# MCU.net
KiCad netlist of a schematic drawn in Altium Designer
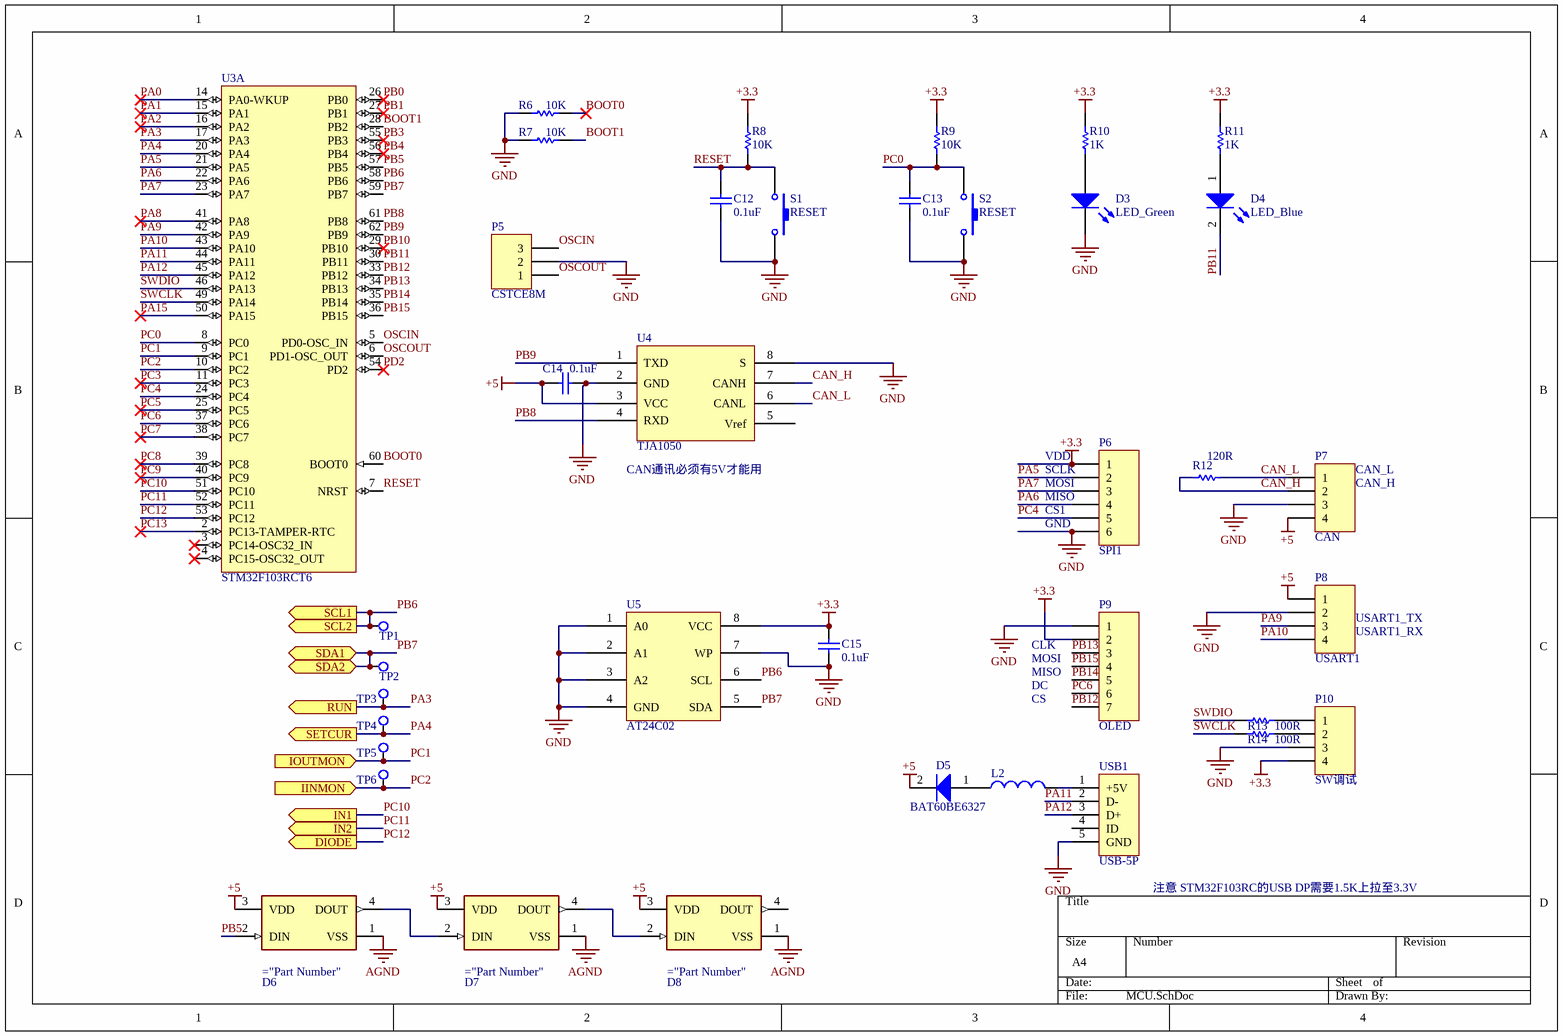
[diagram p0: MCU.SchDoc]

(export (version "E")
  (design (tool "Eeschema 10.0.6"))
  (components
    (comp (ref "C12")
      (value "0.1uF")
      (footprint "0603C")
      (description "X5R 50V")
      (fields (field (name "Comment") "Cap") (field (name "PUBLISHER") "Altium Limited"))
      (libsource (lib "Miscellaneous Devices") (part "Cap"))
    )
    (comp (ref "C13")
      (value "0.1uF")
      (footprint "0603C")
      (description "X5R 50V")
      (fields (field (name "Comment") "Cap") (field (name "PUBLISHER") "Altium Limited"))
      (libsource (lib "Miscellaneous Devices") (part "Cap"))
    )
    (comp (ref "C14")
      (value "0.1uF")
      (footprint "0603C")
      (description "X5R 50V")
      (fields (field (name "Comment") "Cap") (field (name "PUBLISHER") "Altium Limited"))
      (libsource (lib "Miscellaneous Devices") (part "Cap"))
    )
    (comp (ref "C15")
      (value "0.1uF")
      (footprint "0603C")
      (description "X5R 50V")
      (fields (field (name "Comment") "Cap") (field (name "PUBLISHER") "Altium Limited"))
      (libsource (lib "Miscellaneous Devices") (part "Cap"))
    )
    (comp (ref "D3")
      (value "LED_Green")
      (footprint "LED 0603B")
      (description "Green")
      (fields (field (name "PUBLISHER") "Altium Limited"))
      (libsource (lib "Miscellaneous Devices") (part "LED0"))
    )
    (comp (ref "D4")
      (value "LED_Blue")
      (footprint "LED 0603B")
      (description "Blue")
      (fields (field (name "PUBLISHER") "Altium Limited"))
      (libsource (lib "") (part "LED0_1"))
    )
    (comp (ref "D5")
      (value "BAT60BE6327")
      (footprint "SOD-523")
      (description "Diode")
      (fields (field (name "PUBLISHER") "Altium Limited"))
      (libsource (lib "Miscellaneous Devices") (part "Diode"))
    )
    (comp (ref "D6")
      (value "WS2812")
      (footprint "Adafruit_1655_0")
      (description "RGB LED")
      (libsource (lib "MiscDevices_SP") (part "WS2812"))
    )
    (comp (ref "D7")
      (value "WS2812")
      (footprint "Adafruit_1655_0")
      (description "RGB LED")
      (libsource (lib "MiscDevices_SP") (part "WS2812"))
    )
    (comp (ref "D8")
      (value "WS2812")
      (footprint "Adafruit_1655_0")
      (description "RGB LED")
      (libsource (lib "MiscDevices_SP") (part "WS2812"))
    )
    (comp (ref "L2")
      (value "Inductor")
      (footprint "L 0603")
      (description "MPZ1608S181ATAH0")
      (fields (field (name "PUBLISHER") "Altium Limited"))
      (libsource (lib "Miscellaneous Devices") (part "Inductor"))
    )
    (comp (ref "P5")
      (value "CSTCE8M")
      (footprint "CSTCE16M")
      (description "Header, 3-Pin")
      (fields (field (name "PUBLISHER") "Altium Limited"))
      (libsource (lib "Miscellaneous Connectors") (part "Header 3"))
    )
    (comp (ref "P6")
      (value "SPI1")
      (footprint "MX 1.25-WS-6P")
      (description "Header, 6-Pin")
      (fields (field (name "PUBLISHER") "Altium Limited"))
      (libsource (lib "Miscellaneous Connectors") (part "Header 6"))
    )
    (comp (ref "P7")
      (value "CAN")
      (footprint "SM04B")
      (description "Header, 4-Pin")
      (fields (field (name "PUBLISHER") "Altium Limited"))
      (libsource (lib "Miscellaneous Connectors") (part "Header 4"))
    )
    (comp (ref "P8")
      (value "USART1")
      (footprint "SM04B")
      (description "Header, 4-Pin")
      (fields (field (name "PUBLISHER") "Altium Limited"))
      (libsource (lib "Miscellaneous Connectors") (part "Header 4"))
    )
    (comp (ref "P9")
      (value "OLED")
      (footprint "HDR2.54-M-LI-7P")
      (description "OLED Connector 7P杜邦母头")
      (fields (field (name "PUBLISHER") "Altium Limited"))
      (libsource (lib "Miscellaneous Connectors") (part "Header 7"))
    )
    (comp (ref "P10")
      (value "SW调试")
      (footprint "53261")
      (description "Connector MX1.25 4P")
      (fields (field (name "PUBLISHER") "Altium Limited"))
      (libsource (lib "Miscellaneous Connectors") (part "Header 4"))
    )
    (comp (ref "R6")
      (value "10K")
      (footprint "0603R")
      (description "Resistor")
      (fields (field (name "Comment") "Res1") (field (name "PUBLISHER") "Altium Limited"))
      (libsource (lib "Miscellaneous Devices") (part "Res1"))
    )
    (comp (ref "R7")
      (value "10K")
      (footprint "0603R")
      (description "Resistor")
      (fields (field (name "Comment") "Res1") (field (name "PUBLISHER") "Altium Limited"))
      (libsource (lib "Miscellaneous Devices") (part "Res1"))
    )
    (comp (ref "R8")
      (value "10K")
      (footprint "0603R")
      (description "Resistor")
      (fields (field (name "Comment") "Res1") (field (name "PUBLISHER") "Altium Limited"))
      (libsource (lib "Miscellaneous Devices") (part "Res1"))
    )
    (comp (ref "R9")
      (value "10K")
      (footprint "0603R")
      (description "Resistor")
      (fields (field (name "Comment") "Res1") (field (name "PUBLISHER") "Altium Limited"))
      (libsource (lib "Miscellaneous Devices") (part "Res1"))
    )
    (comp (ref "R10")
      (value "1K")
      (footprint "0603R")
      (description "Resistor")
      (fields (field (name "Comment") "Res1") (field (name "PUBLISHER") "Altium Limited"))
      (libsource (lib "Miscellaneous Devices") (part "Res1"))
    )
    (comp (ref "R11")
      (value "1K")
      (footprint "0603R")
      (description "Resistor")
      (fields (field (name "Comment") "Res1") (field (name "PUBLISHER") "Altium Limited"))
      (libsource (lib "Miscellaneous Devices") (part "Res1"))
    )
    (comp (ref "R12")
      (value "120R")
      (footprint "0603R")
      (description "Resistor")
      (fields (field (name "Comment") "Res1") (field (name "PUBLISHER") "Altium Limited"))
      (libsource (lib "") (part "Res1_1"))
    )
    (comp (ref "R13")
      (value "100R")
      (footprint "0603R")
      (description "Resistor")
      (fields (field (name "Comment") "Res1") (field (name "PUBLISHER") "Altium Limited"))
      (libsource (lib "Miscellaneous Devices") (part "Res1"))
    )
    (comp (ref "R14")
      (value "100R")
      (footprint "0603R")
      (description "Resistor")
      (fields (field (name "Comment") "Res1") (field (name "PUBLISHER") "Altium Limited"))
      (libsource (lib "Miscellaneous Devices") (part "Res1"))
    )
    (comp (ref "S1")
      (value "RESET")
      (footprint "TSW SMD-3*6*2.5")
      (description "Switch")
      (fields (field (name "PUBLISHER") "Altium Limited"))
      (libsource (lib "Miscellaneous Devices") (part "SW-PB"))
    )
    (comp (ref "S2")
      (value "RESET")
      (footprint "TSW SMD-3*6*2.5")
      (description "Switch")
      (fields (field (name "PUBLISHER") "Altium Limited"))
      (libsource (lib "Miscellaneous Devices") (part "SW-PB"))
    )
    (comp (ref "TP1")
      (value "TestPoint")
      (footprint "TP_Black(1.6mm)")
      (description "PCB测试点")
      (libsource (lib "MiscDevices_SP") (part "TestPoint"))
    )
    (comp (ref "TP2")
      (value "TestPoint")
      (footprint "TP_Black(1.6mm)")
      (description "PCB测试点")
      (libsource (lib "MiscDevices_SP") (part "TestPoint"))
    )
    (comp (ref "TP3")
      (value "TestPoint")
      (footprint "TP_Black(1.6mm)")
      (description "PCB测试点")
      (libsource (lib "MiscDevices_SP") (part "TestPoint"))
    )
    (comp (ref "TP4")
      (value "TestPoint")
      (footprint "TP_Black(1.6mm)")
      (description "PCB测试点")
      (libsource (lib "MiscDevices_SP") (part "TestPoint"))
    )
    (comp (ref "TP5")
      (value "TestPoint")
      (footprint "TP_Black(1.6mm)")
      (description "PCB测试点")
      (libsource (lib "MiscDevices_SP") (part "TestPoint"))
    )
    (comp (ref "TP6")
      (value "TestPoint")
      (footprint "TP_Black(1.6mm)")
      (description "PCB测试点")
      (libsource (lib "MiscDevices_SP") (part "TestPoint"))
    )
    (comp (ref "U3")
      (value "STM32F103RCT6")
      (footprint "STM-LQFP64_N")
      (libsource (lib "STMicroelectronics STM32 F1") (part "STM32F103RCT6"))
    )
    (comp (ref "U4")
      (value "TJA1050")
      (footprint "SO8")
      (description "CAN收发器")
      (libsource (lib "MiscDevices_SP") (part "TJA1050"))
    )
    (comp (ref "U5") (value "AT24C02") (footprint "SOP8") (libsource (lib "MiscDevices_SP") (part "AT24C02")))
    (comp (ref "USB1")
      (value "USB-5P")
      (footprint "USB-MICRO_E")
      (description "微型USB母座")
      (fields (field (name "版权归属") "源创客"))
      (libsource (lib "4.1   - 接口类") (part "USB-5P"))
    )
  )
  (nets
    (net (code "1") (name "+3.3") (class "Default")
      (node (ref "C15") (pin "1") (pinfunction "1_1") (pintype "passive"))
      (node (ref "P10") (pin "4") (pinfunction "4_4") (pintype "passive"))
      (node (ref "P6") (pin "1") (pinfunction "1_1") (pintype "passive"))
      (node (ref "P9") (pin "2") (pinfunction "2_2") (pintype "passive"))
      (node (ref "R10") (pin "2") (pinfunction "2_2") (pintype "passive"))
      (node (ref "R11") (pin "2") (pinfunction "2_2") (pintype "passive"))
      (node (ref "R8") (pin "2") (pinfunction "2_2") (pintype "passive"))
      (node (ref "R9") (pin "2") (pinfunction "2_2") (pintype "passive"))
      (node (ref "U5") (pin "8") (pinfunction "VCC_8") (pintype "passive"))
    )
    (net (code "2") (name "+5") (class "Default")
      (node (ref "C14") (pin "2") (pinfunction "2_2") (pintype "passive"))
      (node (ref "D5") (pin "2") (pinfunction "K_2") (pintype "passive"))
      (node (ref "D6") (pin "3") (pinfunction "VDD_3") (pintype "power_in"))
      (node (ref "D7") (pin "3") (pinfunction "VDD_3") (pintype "power_in"))
      (node (ref "D8") (pin "3") (pinfunction "VDD_3") (pintype "power_in"))
      (node (ref "P7") (pin "4") (pinfunction "4_4") (pintype "passive"))
      (node (ref "P8") (pin "1") (pinfunction "1_1") (pintype "passive"))
      (node (ref "U4") (pin "3") (pinfunction "VCC_3") (pintype "passive"))
    )
    (net (code "3") (name "/BOOT0") (class "Default")
      (node (ref "R6") (pin "2") (pinfunction "2_2") (pintype "passive"))
      (node (ref "U3") (pin "60") (pinfunction "BOOT0_60") (pintype "input"))
    )
    (net (code "4") (name "/BOOT1") (class "Default")
      (node (ref "R7") (pin "2") (pinfunction "2_2") (pintype "passive"))
      (node (ref "U3") (pin "28") (pinfunction "PB2_28") (pintype "bidirectional"))
    )
    (net (code "5") (name "/CAN_H") (class "Default")
      (node (ref "P7") (pin "2") (pinfunction "2_2") (pintype "passive"))
      (node (ref "R12") (pin "1") (pinfunction "1_1") (pintype "passive"))
      (node (ref "U4") (pin "7") (pinfunction "CANH_7") (pintype "passive"))
    )
    (net (code "6") (name "/CAN_L") (class "Default")
      (node (ref "P7") (pin "1") (pinfunction "1_1") (pintype "passive"))
      (node (ref "R12") (pin "2") (pinfunction "2_2") (pintype "passive"))
      (node (ref "U4") (pin "6") (pinfunction "CANL_6") (pintype "passive"))
    )
    (net (code "7") (name "/OSCIN") (class "Default")
      (node (ref "P5") (pin "3") (pinfunction "3_3") (pintype "passive"))
      (node (ref "U3") (pin "5") (pinfunction "PD0-OSC_IN_5") (pintype "bidirectional"))
    )
    (net (code "8") (name "/OSCOUT") (class "Default")
      (node (ref "P5") (pin "1") (pinfunction "1_1") (pintype "passive"))
      (node (ref "U3") (pin "6") (pinfunction "PD1-OSC_OUT_6") (pintype "bidirectional"))
    )
    (net (code "9") (name "/PA0") (class "Default")
      (node (ref "U3") (pin "14") (pinfunction "PA0-WKUP_14") (pintype "bidirectional+no_connect"))
    )
    (net (code "10") (name "/PA1") (class "Default")
      (node (ref "U3") (pin "15") (pinfunction "PA1_15") (pintype "bidirectional+no_connect"))
    )
    (net (code "11") (name "/PA2") (class "Default")
      (node (ref "U3") (pin "16") (pinfunction "PA2_16") (pintype "bidirectional+no_connect"))
    )
    (net (code "12") (name "/PA3") (class "Default")
      (node (ref "TP3") (pin "1") (pinfunction "VSS_1") (pintype "passive"))
      (node (ref "U3") (pin "17") (pinfunction "PA3_17") (pintype "bidirectional"))
    )
    (net (code "13") (name "/PA4") (class "Default")
      (node (ref "TP4") (pin "1") (pinfunction "VSS_1") (pintype "passive"))
      (node (ref "U3") (pin "20") (pinfunction "PA4_20") (pintype "bidirectional"))
    )
    (net (code "14") (name "/PA5") (class "Default")
      (node (ref "P6") (pin "2") (pinfunction "2_2") (pintype "passive"))
      (node (ref "U3") (pin "21") (pinfunction "PA5_21") (pintype "bidirectional"))
    )
    (net (code "15") (name "/PA6") (class "Default")
      (node (ref "P6") (pin "4") (pinfunction "4_4") (pintype "passive"))
      (node (ref "U3") (pin "22") (pinfunction "PA6_22") (pintype "bidirectional"))
    )
    (net (code "16") (name "/PA7") (class "Default")
      (node (ref "P6") (pin "3") (pinfunction "3_3") (pintype "passive"))
      (node (ref "U3") (pin "23") (pinfunction "PA7_23") (pintype "bidirectional"))
    )
    (net (code "17") (name "/PA8") (class "Default")
      (node (ref "U3") (pin "41") (pinfunction "PA8_41") (pintype "bidirectional+no_connect"))
    )
    (net (code "18") (name "/PA9") (class "Default")
      (node (ref "P8") (pin "3") (pinfunction "3_3") (pintype "passive"))
      (node (ref "U3") (pin "42") (pinfunction "PA9_42") (pintype "bidirectional"))
    )
    (net (code "19") (name "/PA10") (class "Default")
      (node (ref "P8") (pin "4") (pinfunction "4_4") (pintype "passive"))
      (node (ref "U3") (pin "43") (pinfunction "PA10_43") (pintype "bidirectional"))
    )
    (net (code "20") (name "/PA11") (class "Default")
      (node (ref "U3") (pin "44") (pinfunction "PA11_44") (pintype "bidirectional"))
      (node (ref "USB1") (pin "2") (pinfunction "D-_2") (pintype "passive"))
    )
    (net (code "21") (name "/PA12") (class "Default")
      (node (ref "U3") (pin "45") (pinfunction "PA12_45") (pintype "bidirectional"))
      (node (ref "USB1") (pin "3") (pinfunction "D+_3") (pintype "passive"))
    )
    (net (code "22") (name "/PA15") (class "Default")
      (node (ref "U3") (pin "50") (pinfunction "PA15_50") (pintype "bidirectional+no_connect"))
    )
    (net (code "23") (name "/PB0") (class "Default")
      (node (ref "U3") (pin "26") (pinfunction "PB0_26") (pintype "bidirectional+no_connect"))
    )
    (net (code "24") (name "/PB1") (class "Default")
      (node (ref "U3") (pin "27") (pinfunction "PB1_27") (pintype "bidirectional+no_connect"))
    )
    (net (code "25") (name "/PB3") (class "Default")
      (node (ref "U3") (pin "55") (pinfunction "PB3_55") (pintype "bidirectional+no_connect"))
    )
    (net (code "26") (name "/PB4") (class "Default")
      (node (ref "U3") (pin "56") (pinfunction "PB4_56") (pintype "bidirectional+no_connect"))
    )
    (net (code "27") (name "/PB5") (class "Default")
      (node (ref "D6") (pin "2") (pinfunction "DIN_2") (pintype "input"))
      (node (ref "U3") (pin "57") (pinfunction "PB5_57") (pintype "bidirectional"))
    )
    (net (code "28") (name "/PB6") (class "Default")
      (node (ref "TP1") (pin "1") (pinfunction "VSS_1") (pintype "passive"))
      (node (ref "U3") (pin "58") (pinfunction "PB6_58") (pintype "bidirectional"))
      (node (ref "U5") (pin "6") (pinfunction "SCL_6") (pintype "passive"))
    )
    (net (code "29") (name "/PB7") (class "Default")
      (node (ref "TP2") (pin "1") (pinfunction "VSS_1") (pintype "passive"))
      (node (ref "U3") (pin "59") (pinfunction "PB7_59") (pintype "bidirectional"))
      (node (ref "U5") (pin "5") (pinfunction "SDA_5") (pintype "passive"))
    )
    (net (code "30") (name "/PB8") (class "Default")
      (node (ref "U3") (pin "61") (pinfunction "PB8_61") (pintype "bidirectional"))
      (node (ref "U4") (pin "4") (pinfunction "RXD_4") (pintype "passive"))
    )
    (net (code "31") (name "/PB9") (class "Default")
      (node (ref "U3") (pin "62") (pinfunction "PB9_62") (pintype "bidirectional"))
      (node (ref "U4") (pin "1") (pinfunction "TXD_1") (pintype "passive"))
    )
    (net (code "32") (name "/PB10") (class "Default")
      (node (ref "U3") (pin "29") (pinfunction "PB10_29") (pintype "bidirectional+no_connect"))
    )
    (net (code "33") (name "/PB11") (class "Default")
      (node (ref "D4") (pin "2") (pinfunction "K_2") (pintype "passive"))
      (node (ref "U3") (pin "30") (pinfunction "PB11_30") (pintype "bidirectional"))
    )
    (net (code "34") (name "/PB12") (class "Default")
      (node (ref "P9") (pin "7") (pinfunction "7_7") (pintype "passive"))
      (node (ref "U3") (pin "33") (pinfunction "PB12_33") (pintype "bidirectional"))
    )
    (net (code "35") (name "/PB13") (class "Default")
      (node (ref "P9") (pin "3") (pinfunction "3_3") (pintype "passive"))
      (node (ref "U3") (pin "34") (pinfunction "PB13_34") (pintype "bidirectional"))
    )
    (net (code "36") (name "/PB14") (class "Default")
      (node (ref "P9") (pin "5") (pinfunction "5_5") (pintype "passive"))
      (node (ref "U3") (pin "35") (pinfunction "PB14_35") (pintype "bidirectional"))
    )
    (net (code "37") (name "/PB15") (class "Default")
      (node (ref "P9") (pin "4") (pinfunction "4_4") (pintype "passive"))
      (node (ref "U3") (pin "36") (pinfunction "PB15_36") (pintype "bidirectional"))
    )
    (net (code "38") (name "/PC0") (class "Default")
      (node (ref "C13") (pin "2") (pinfunction "2_2") (pintype "passive"))
      (node (ref "R9") (pin "1") (pinfunction "1_1") (pintype "passive"))
      (node (ref "S2") (pin "1") (pinfunction "1_1") (pintype "passive"))
      (node (ref "U3") (pin "8") (pinfunction "PC0_8") (pintype "bidirectional"))
    )
    (net (code "39") (name "/PC1") (class "Default")
      (node (ref "TP5") (pin "1") (pinfunction "VSS_1") (pintype "passive"))
      (node (ref "U3") (pin "9") (pinfunction "PC1_9") (pintype "bidirectional"))
    )
    (net (code "40") (name "/PC2") (class "Default")
      (node (ref "TP6") (pin "1") (pinfunction "VSS_1") (pintype "passive"))
      (node (ref "U3") (pin "10") (pinfunction "PC2_10") (pintype "bidirectional"))
    )
    (net (code "41") (name "/PC3") (class "Default")
      (node (ref "U3") (pin "11") (pinfunction "PC3_11") (pintype "bidirectional+no_connect"))
    )
    (net (code "42") (name "/PC4") (class "Default")
      (node (ref "P6") (pin "5") (pinfunction "5_5") (pintype "passive"))
      (node (ref "U3") (pin "24") (pinfunction "PC4_24") (pintype "bidirectional"))
    )
    (net (code "43") (name "/PC5") (class "Default")
      (node (ref "U3") (pin "25") (pinfunction "PC5_25") (pintype "bidirectional+no_connect"))
    )
    (net (code "44") (name "/PC6") (class "Default")
      (node (ref "P9") (pin "6") (pinfunction "6_6") (pintype "passive"))
      (node (ref "U3") (pin "37") (pinfunction "PC6_37") (pintype "bidirectional"))
    )
    (net (code "45") (name "/PC7") (class "Default")
      (node (ref "U3") (pin "38") (pinfunction "PC7_38") (pintype "bidirectional+no_connect"))
    )
    (net (code "46") (name "/PC8") (class "Default")
      (node (ref "U3") (pin "39") (pinfunction "PC8_39") (pintype "bidirectional+no_connect"))
    )
    (net (code "47") (name "/PC9") (class "Default")
      (node (ref "U3") (pin "40") (pinfunction "PC9_40") (pintype "bidirectional+no_connect"))
    )
    (net (code "48") (name "/PC10") (class "Default")
      (node (ref "U3") (pin "51") (pinfunction "PC10_51") (pintype "bidirectional"))
    )
    (net (code "49") (name "/PC11") (class "Default")
      (node (ref "U3") (pin "52") (pinfunction "PC11_52") (pintype "bidirectional"))
    )
    (net (code "50") (name "/PC12") (class "Default")
      (node (ref "U3") (pin "53") (pinfunction "PC12_53") (pintype "bidirectional"))
    )
    (net (code "51") (name "/PC13") (class "Default")
      (node (ref "U3") (pin "2") (pinfunction "PC13-TAMPER-RTC_2") (pintype "bidirectional+no_connect"))
    )
    (net (code "52") (name "/PD2") (class "Default")
      (node (ref "U3") (pin "54") (pinfunction "PD2_54") (pintype "bidirectional+no_connect"))
    )
    (net (code "53") (name "/RESET") (class "Default")
      (node (ref "C12") (pin "2") (pinfunction "2_2") (pintype "passive"))
      (node (ref "R8") (pin "1") (pinfunction "1_1") (pintype "passive"))
      (node (ref "S1") (pin "1") (pinfunction "1_1") (pintype "passive"))
      (node (ref "U3") (pin "7") (pinfunction "NRST_7") (pintype "bidirectional"))
    )
    (net (code "54") (name "/SWCLK") (class "Default")
      (node (ref "R14") (pin "1") (pinfunction "1_1") (pintype "passive"))
      (node (ref "U3") (pin "49") (pinfunction "PA14_49") (pintype "bidirectional"))
    )
    (net (code "55") (name "/SWDIO") (class "Default")
      (node (ref "R13") (pin "1") (pinfunction "1_1") (pintype "passive"))
      (node (ref "U3") (pin "46") (pinfunction "PA13_46") (pintype "bidirectional"))
    )
    (net (code "56") (name "AGND") (class "Default")
      (node (ref "D6") (pin "1") (pinfunction "VSS_1") (pintype "power_in"))
      (node (ref "D7") (pin "1") (pinfunction "VSS_1") (pintype "power_in"))
      (node (ref "D8") (pin "1") (pinfunction "VSS_1") (pintype "power_in"))
    )
    (net (code "57") (name "GND") (class "Default")
      (node (ref "C12") (pin "1") (pinfunction "1_1") (pintype "passive"))
      (node (ref "C13") (pin "1") (pinfunction "1_1") (pintype "passive"))
      (node (ref "C14") (pin "1") (pinfunction "1_1") (pintype "passive"))
      (node (ref "C15") (pin "2") (pinfunction "2_2") (pintype "passive"))
      (node (ref "D3") (pin "2") (pinfunction "K_2") (pintype "passive"))
      (node (ref "P10") (pin "3") (pinfunction "3_3") (pintype "passive"))
      (node (ref "P5") (pin "2") (pinfunction "2_2") (pintype "passive"))
      (node (ref "P6") (pin "6") (pinfunction "6_6") (pintype "passive"))
      (node (ref "P7") (pin "3") (pinfunction "3_3") (pintype "passive"))
      (node (ref "P8") (pin "2") (pinfunction "2_2") (pintype "passive"))
      (node (ref "P9") (pin "1") (pinfunction "1_1") (pintype "passive"))
      (node (ref "R6") (pin "1") (pinfunction "1_1") (pintype "passive"))
      (node (ref "R7") (pin "1") (pinfunction "1_1") (pintype "passive"))
      (node (ref "S1") (pin "2") (pinfunction "2_2") (pintype "passive"))
      (node (ref "S2") (pin "2") (pinfunction "2_2") (pintype "passive"))
      (node (ref "U4") (pin "2") (pinfunction "GND_2") (pintype "passive"))
      (node (ref "U4") (pin "8") (pinfunction "S_8") (pintype "passive"))
      (node (ref "U5") (pin "1") (pinfunction "A0_1") (pintype "passive"))
      (node (ref "U5") (pin "2") (pinfunction "A1_2") (pintype "passive"))
      (node (ref "U5") (pin "3") (pinfunction "A2_3") (pintype "passive"))
      (node (ref "U5") (pin "4") (pinfunction "GND_4") (pintype "passive"))
      (node (ref "U5") (pin "7") (pinfunction "WP_7") (pintype "passive"))
      (node (ref "USB1") (pin "5") (pinfunction "GND_5") (pintype "passive"))
    )
    (net (code "58") (name "Net-(D3-A)") (class "Default")
      (node (ref "D3") (pin "1") (pinfunction "A_1") (pintype "passive"))
      (node (ref "R10") (pin "1") (pinfunction "1_1") (pintype "passive"))
    )
    (net (code "59") (name "Net-(D4-A)") (class "Default")
      (node (ref "D4") (pin "1") (pinfunction "A_1") (pintype "passive"))
      (node (ref "R11") (pin "1") (pinfunction "1_1") (pintype "passive"))
    )
    (net (code "60") (name "Net-(D5-A)") (class "Default")
      (node (ref "D5") (pin "1") (pinfunction "A_1") (pintype "passive"))
      (node (ref "L2") (pin "1") (pinfunction "1_1") (pintype "passive"))
    )
    (net (code "61") (name "Net-(D6-DOUT)") (class "Default")
      (node (ref "D6") (pin "4") (pinfunction "DOUT_4") (pintype "output"))
      (node (ref "D7") (pin "2") (pinfunction "DIN_2") (pintype "input"))
    )
    (net (code "62") (name "Net-(D7-DOUT)") (class "Default")
      (node (ref "D7") (pin "4") (pinfunction "DOUT_4") (pintype "output"))
      (node (ref "D8") (pin "2") (pinfunction "DIN_2") (pintype "input"))
    )
    (net (code "63") (name "Net-(P10-Pad1)") (class "Default")
      (node (ref "P10") (pin "1") (pinfunction "1_1") (pintype "passive"))
      (node (ref "R13") (pin "2") (pinfunction "2_2") (pintype "passive"))
    )
    (net (code "64") (name "Net-(P10-Pad2)") (class "Default")
      (node (ref "P10") (pin "2") (pinfunction "2_2") (pintype "passive"))
      (node (ref "R14") (pin "2") (pinfunction "2_2") (pintype "passive"))
    )
    (net (code "65") (name "Net-(USB1-+5V)") (class "Default")
      (node (ref "L2") (pin "2") (pinfunction "2_2") (pintype "passive"))
      (node (ref "USB1") (pin "1") (pinfunction "+5V_1") (pintype "passive"))
    )
    (net (code "66") (name "unconnected-(D8-DOUT-Pad4)") (class "Default")
      (node (ref "D8") (pin "4") (pinfunction "DOUT_4") (pintype "output"))
    )
    (net (code "67") (name "unconnected-(U3A-PC14-OSC32_IN-Pad3)") (class "Default")
      (node (ref "U3") (pin "3") (pinfunction "PC14-OSC32_IN_3") (pintype "bidirectional+no_connect"))
    )
    (net (code "68") (name "unconnected-(U3A-PC15-OSC32_OUT-Pad4)") (class "Default")
      (node (ref "U3") (pin "4") (pinfunction "PC15-OSC32_OUT_4") (pintype "bidirectional+no_connect"))
    )
    (net (code "69") (name "unconnected-(U4-Vref-Pad5)") (class "Default")
      (node (ref "U4") (pin "5") (pinfunction "Vref_5") (pintype "passive"))
    )
    (net (code "70") (name "unconnected-(USB1-ID-Pad4)") (class "Default")
      (node (ref "USB1") (pin "4") (pinfunction "ID_4") (pintype "passive"))
    )
  )
)
